# brain.net
KiCad netlist of a schematic drawn in EAGLE
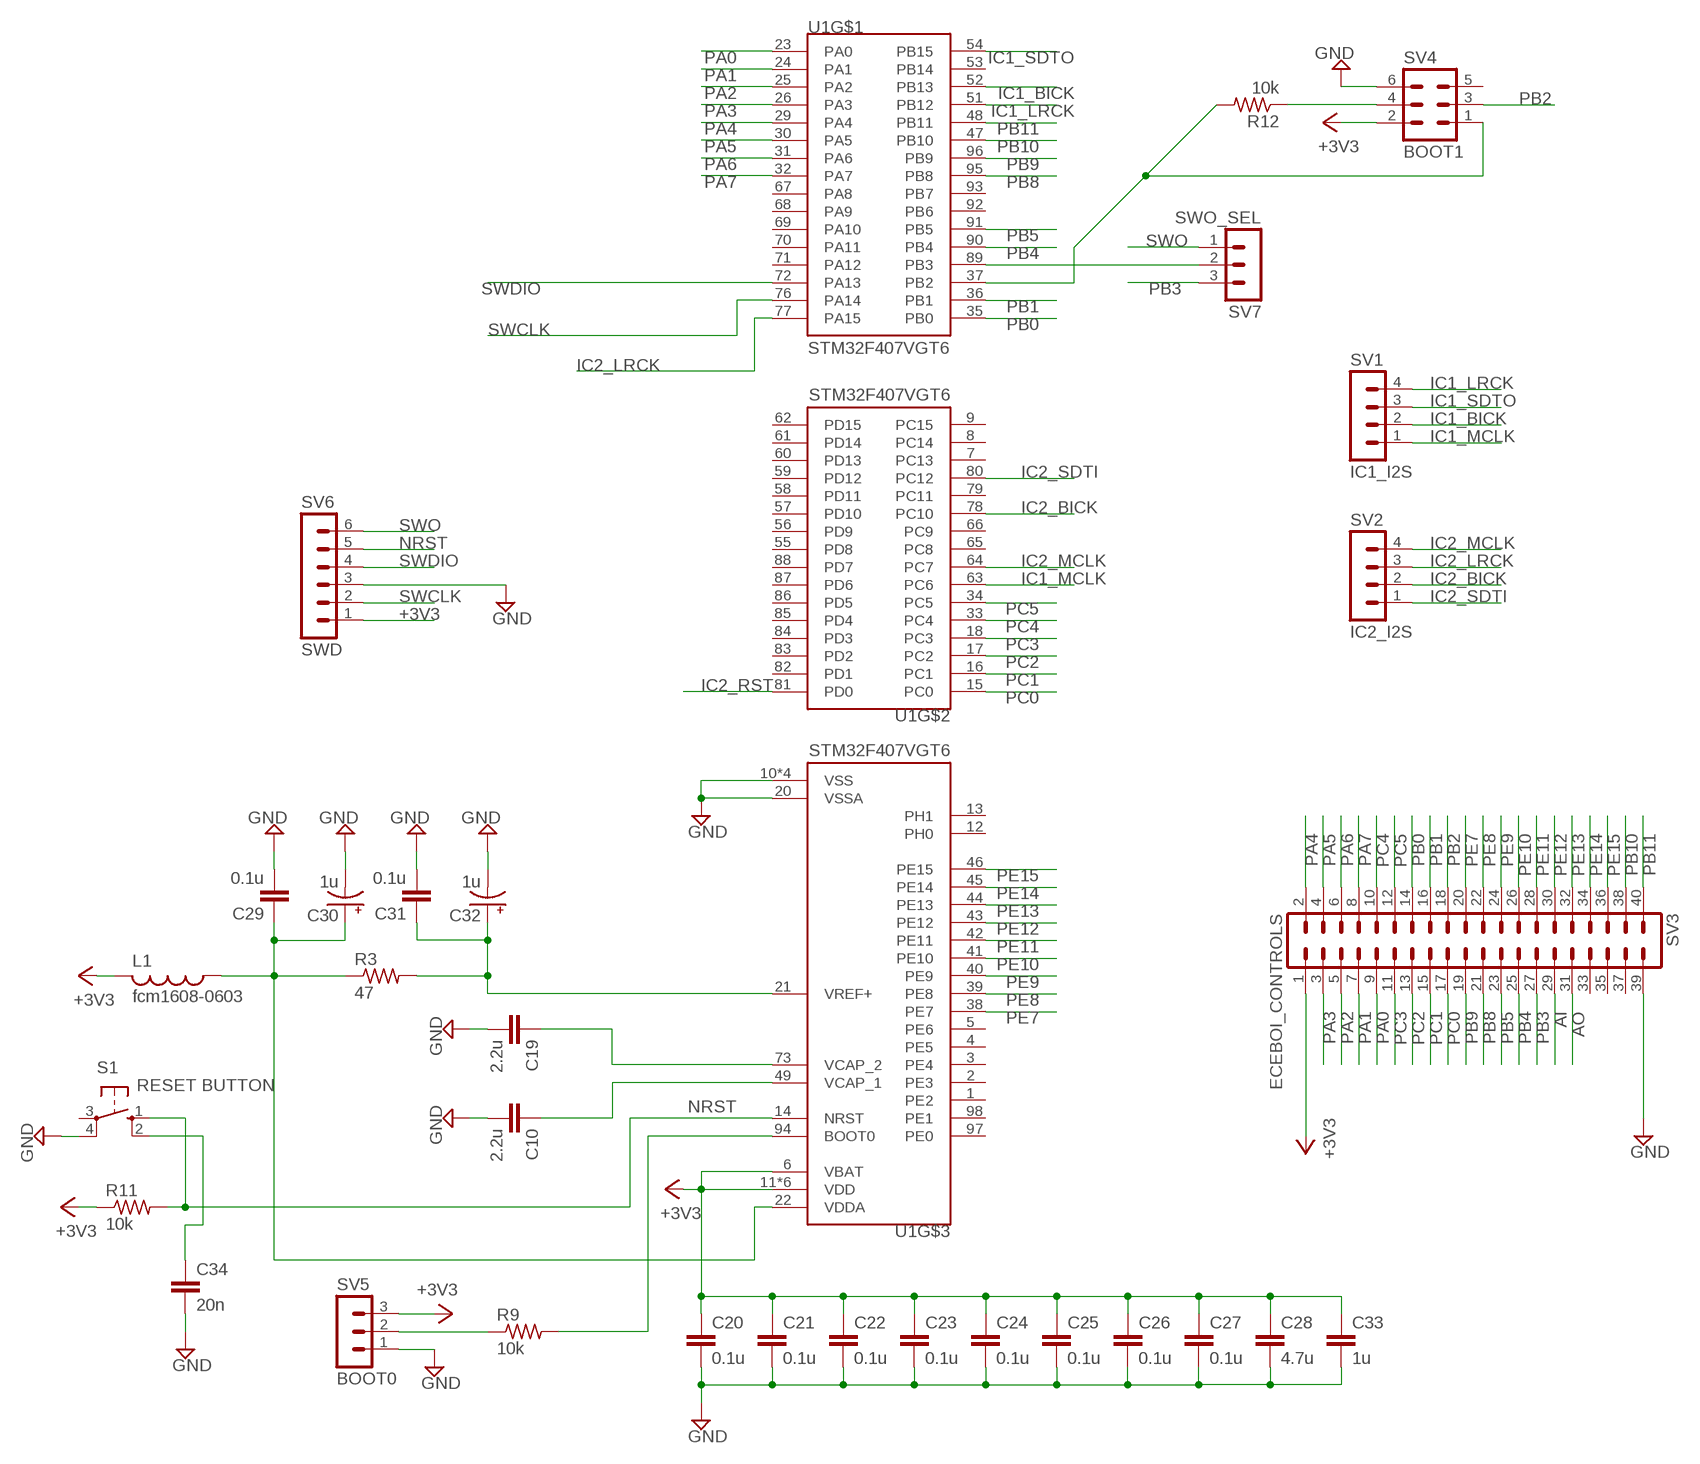
[diagram p0: schematic, sheet 1]
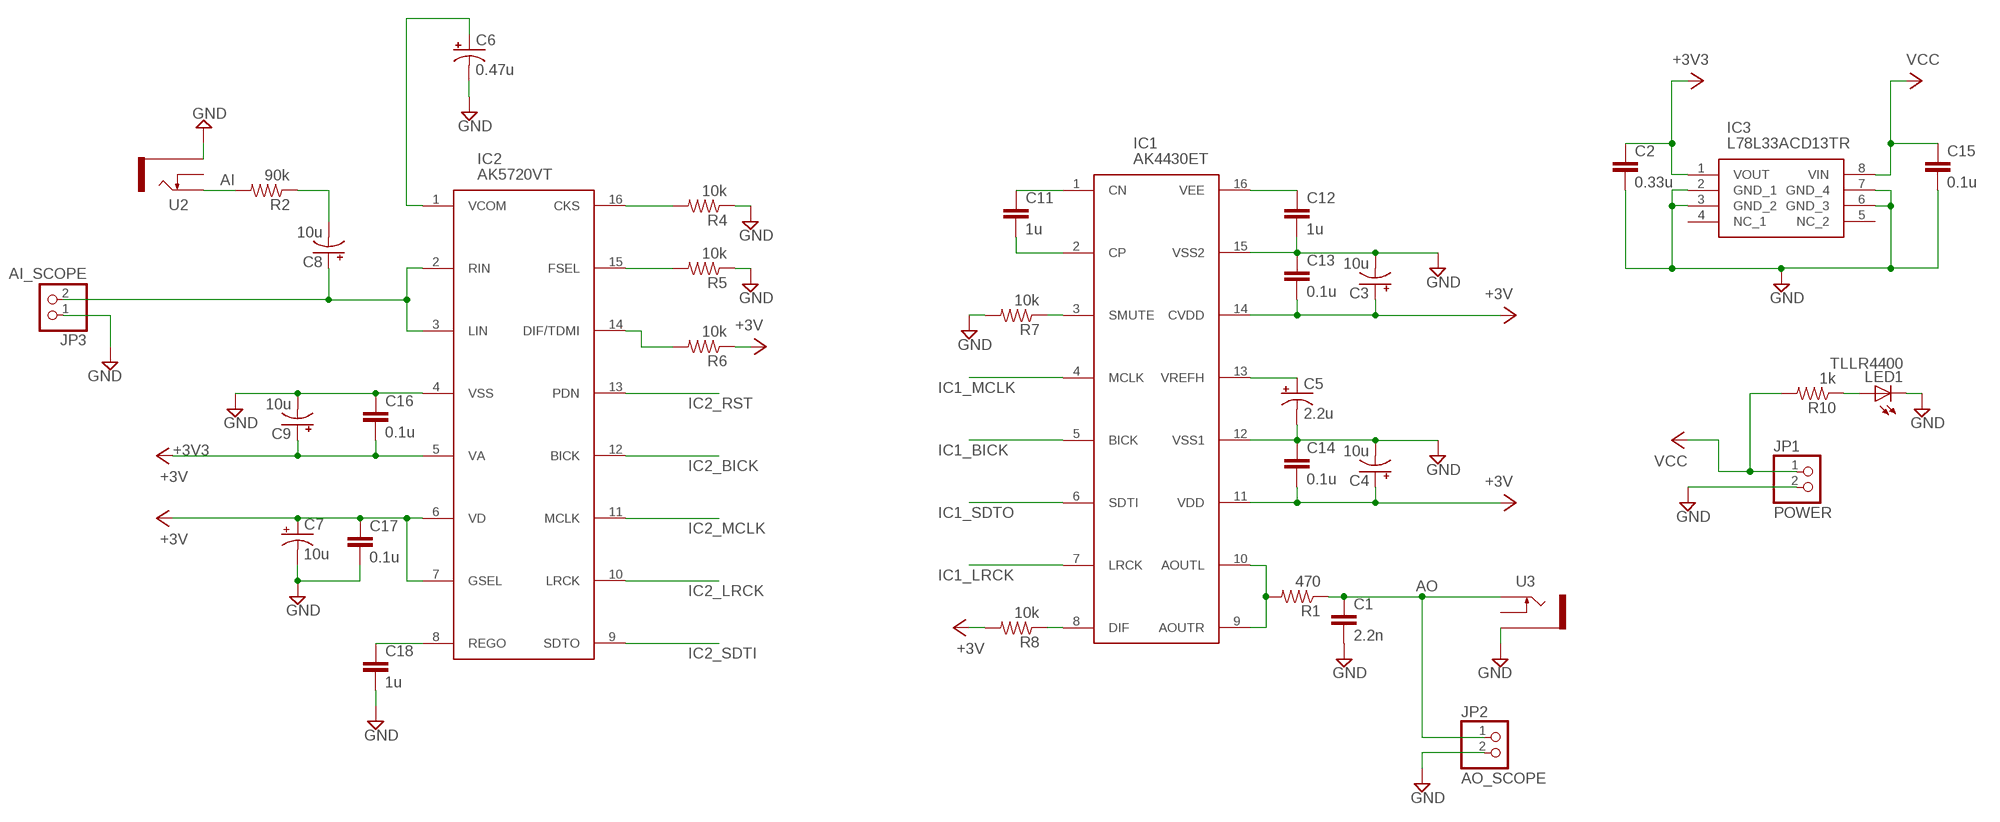
[diagram p1: schematic, sheet 2]

(export (version "E")
  (design (tool "Eeschema 10.0.6"))
  (components
    (comp (ref "C10")
      (value "2.2u")
      (footprint "eagle-import:C025-024X044")
      (libsource (lib "eagle-import") (part "C-EU025-024X044"))
    )
    (comp (ref "C19")
      (value "2.2u")
      (footprint "eagle-import:C025-024X044")
      (libsource (lib "eagle-import") (part "C-EU025-024X044"))
    )
    (comp (ref "C20")
      (value "0.1u")
      (footprint "eagle-import:C025-024X044")
      (libsource (lib "eagle-import") (part "C-EU025-024X044"))
    )
    (comp (ref "C21")
      (value "0.1u")
      (footprint "eagle-import:C025-024X044")
      (libsource (lib "eagle-import") (part "C-EU025-024X044"))
    )
    (comp (ref "C22")
      (value "0.1u")
      (footprint "eagle-import:C025-024X044")
      (libsource (lib "eagle-import") (part "C-EU025-024X044"))
    )
    (comp (ref "C23")
      (value "0.1u")
      (footprint "eagle-import:C025-024X044")
      (libsource (lib "eagle-import") (part "C-EU025-024X044"))
    )
    (comp (ref "C24")
      (value "0.1u")
      (footprint "eagle-import:C025-024X044")
      (libsource (lib "eagle-import") (part "C-EU025-024X044"))
    )
    (comp (ref "C25")
      (value "0.1u")
      (footprint "eagle-import:C025-024X044")
      (libsource (lib "eagle-import") (part "C-EU025-024X044"))
    )
    (comp (ref "C26")
      (value "0.1u")
      (footprint "eagle-import:C025-024X044")
      (libsource (lib "eagle-import") (part "C-EU025-024X044"))
    )
    (comp (ref "C27")
      (value "0.1u")
      (footprint "eagle-import:C025-024X044")
      (libsource (lib "eagle-import") (part "C-EU025-024X044"))
    )
    (comp (ref "C28")
      (value "4.7u")
      (footprint "eagle-import:C025-024X044")
      (libsource (lib "eagle-import") (part "C-EU025-024X044"))
    )
    (comp (ref "C29")
      (value "0.1u")
      (footprint "eagle-import:C025-024X044")
      (libsource (lib "eagle-import") (part "C-EU025-024X044"))
    )
    (comp (ref "C30")
      (value "1u")
      (footprint "eagle-import:E2-5")
      (libsource (lib "eagle-import") (part "CPOL-USE2-5"))
    )
    (comp (ref "C31")
      (value "0.1u")
      (footprint "eagle-import:C025-024X044")
      (libsource (lib "eagle-import") (part "C-EU025-024X044"))
    )
    (comp (ref "C32")
      (value "1u")
      (footprint "eagle-import:E2-5")
      (libsource (lib "eagle-import") (part "CPOL-USE2-5"))
    )
    (comp (ref "C33")
      (value "1u")
      (footprint "eagle-import:C025-024X044")
      (libsource (lib "eagle-import") (part "C-EU025-024X044"))
    )
    (comp (ref "C34")
      (value "20n")
      (footprint "eagle-import:C025-024X044")
      (libsource (lib "eagle-import") (part "C-EU025-024X044"))
    )
    (comp (ref "L1")
      (value "fcm1608-0603")
      (footprint "eagle-import:0207_10")
      (libsource (lib "eagle-import") (part "L-US0207/10"))
    )
    (comp (ref "R3")
      (value "47")
      (footprint "eagle-import:0207_10")
      (libsource (lib "eagle-import") (part "R-US_0207/10"))
    )
    (comp (ref "R9")
      (value "10k")
      (footprint "eagle-import:0207_10")
      (libsource (lib "eagle-import") (part "R-US_0207/10"))
    )
    (comp (ref "R11")
      (value "10k")
      (footprint "eagle-import:0207_10")
      (libsource (lib "eagle-import") (part "R-US_0207/10"))
    )
    (comp (ref "R12")
      (value "10k")
      (footprint "eagle-import:0207_10")
      (libsource (lib "eagle-import") (part "R-US_0207/10"))
    )
    (comp (ref "S1")
      (value "RESET BUTTON")
      (footprint "eagle-import:B3F-10XX")
      (fields (field (name "MPN") "B3F-1000"))
      (libsource (lib "eagle-import") (part "10-XX"))
    )
    (comp (ref "SV1")
      (value "IC1_I2S")
      (footprint "eagle-import:MA04-1")
      (libsource (lib "eagle-import") (part "MA04-1"))
    )
    (comp (ref "SV2")
      (value "IC2_I2S")
      (footprint "eagle-import:MA04-1")
      (libsource (lib "eagle-import") (part "MA04-1"))
    )
    (comp (ref "SV3")
      (value "ECEBOI_CONTROLS")
      (footprint "eagle-import:MA20-2")
      (libsource (lib "eagle-import") (part "MA20-2"))
    )
    (comp (ref "SV4")
      (value "BOOT1")
      (footprint "eagle-import:MA03-2")
      (libsource (lib "eagle-import") (part "MA03-2"))
    )
    (comp (ref "SV5")
      (value "BOOT0")
      (footprint "eagle-import:MA03-1")
      (libsource (lib "eagle-import") (part "MA03-1"))
    )
    (comp (ref "SV6")
      (value "SWD")
      (footprint "eagle-import:MA06-1")
      (libsource (lib "eagle-import") (part "MA06-1"))
    )
    (comp (ref "SV7")
      (value "SWO_SEL")
      (footprint "eagle-import:MA03-1")
      (libsource (lib "eagle-import") (part "MA03-1"))
    )
    (comp (ref "U1")
      (value "STM32F407VGT6")
      (footprint "eagle-import:QFP50P1600X1600X160-100N")
      (fields (field (name "DIGI-KEY_PART_NUMBER") "497-11605-ND") (field (name "MF") "STMicroelectronics"))
      (libsource (lib "eagle-import") (part "STM32F407VGT6"))
    )
    (comp (ref "C1")
      (value "2.2n")
      (footprint "eagle-import:C025-024X044")
      (libsource (lib "eagle-import") (part "C-EU025-024X044"))
    )
    (comp (ref "C2")
      (value "0.33u")
      (footprint "eagle-import:C025-024X044")
      (libsource (lib "eagle-import") (part "C-EU025-024X044"))
    )
    (comp (ref "C3")
      (value "10u")
      (footprint "eagle-import:E2-5")
      (libsource (lib "eagle-import") (part "CPOL-USE2-5"))
    )
    (comp (ref "C4")
      (value "10u")
      (footprint "eagle-import:E2-5")
      (libsource (lib "eagle-import") (part "CPOL-USE2-5"))
    )
    (comp (ref "C5")
      (value "2.2u")
      (footprint "eagle-import:E2-5")
      (libsource (lib "eagle-import") (part "CPOL-USE2-5"))
    )
    (comp (ref "C6")
      (value "0.47u")
      (footprint "eagle-import:E2-5")
      (libsource (lib "eagle-import") (part "CPOL-USE2-5"))
    )
    (comp (ref "C7")
      (value "10u")
      (footprint "eagle-import:E2-5")
      (libsource (lib "eagle-import") (part "CPOL-USE2-5"))
    )
    (comp (ref "C8")
      (value "10u")
      (footprint "eagle-import:E2-5")
      (libsource (lib "eagle-import") (part "CPOL-USE2-5"))
    )
    (comp (ref "C9")
      (value "10u")
      (footprint "eagle-import:E2-5")
      (libsource (lib "eagle-import") (part "CPOL-USE2-5"))
    )
    (comp (ref "C11")
      (value "1u")
      (footprint "eagle-import:C025-024X044")
      (libsource (lib "eagle-import") (part "C-EU025-024X044"))
    )
    (comp (ref "C12")
      (value "1u")
      (footprint "eagle-import:C025-024X044")
      (libsource (lib "eagle-import") (part "C-EU025-024X044"))
    )
    (comp (ref "C13")
      (value "0.1u")
      (footprint "eagle-import:C025-024X044")
      (libsource (lib "eagle-import") (part "C-EU025-024X044"))
    )
    (comp (ref "C14")
      (value "0.1u")
      (footprint "eagle-import:C025-024X044")
      (libsource (lib "eagle-import") (part "C-EU025-024X044"))
    )
    (comp (ref "C15")
      (value "0.1u")
      (footprint "eagle-import:C025-024X044")
      (libsource (lib "eagle-import") (part "C-EU025-024X044"))
    )
    (comp (ref "C16")
      (value "0.1u")
      (footprint "eagle-import:C025-024X044")
      (libsource (lib "eagle-import") (part "C-EU025-024X044"))
    )
    (comp (ref "C17")
      (value "0.1u")
      (footprint "eagle-import:C025-024X044")
      (libsource (lib "eagle-import") (part "C-EU025-024X044"))
    )
    (comp (ref "C18")
      (value "1u")
      (footprint "eagle-import:C025-024X044")
      (libsource (lib "eagle-import") (part "C-EU025-024X044"))
    )
    (comp (ref "IC1")
      (value "AK4430ET")
      (footprint "eagle-import:SOP65P640X110-16N")
      (libsource (lib "eagle-import") (part "AK4430ET"))
    )
    (comp (ref "IC2")
      (value "AK5720VT")
      (footprint "eagle-import:SOP65P640X110-16N")
      (libsource (lib "eagle-import") (part "AK5720VT"))
    )
    (comp (ref "IC3")
      (value "L78L33ACD13TR")
      (footprint "eagle-import:SOIC127P600X175-8N")
      (libsource (lib "eagle-import") (part "L78L33ACD13TR"))
    )
    (comp (ref "JP1")
      (value "POWER")
      (footprint "eagle-import:1X02")
      (libsource (lib "eagle-import") (part "PINHD-1X2"))
    )
    (comp (ref "JP2")
      (value "AO_SCOPE")
      (footprint "eagle-import:1X02")
      (libsource (lib "eagle-import") (part "pinhead_325_PINHD-1X2"))
    )
    (comp (ref "JP3")
      (value "AI_SCOPE")
      (footprint "eagle-import:1X02")
      (libsource (lib "eagle-import") (part "pinhead_325_PINHD-1X2"))
    )
    (comp (ref "LED1")
      (value "TLLR4400")
      (footprint "eagle-import:LED3MM")
      (fields (field (name "MF") "VISHAY SEMICONDUCTOR"))
      (libsource (lib "eagle-import") (part "TLLR4400"))
    )
    (comp (ref "R1")
      (value "470")
      (footprint "eagle-import:0207_10")
      (libsource (lib "eagle-import") (part "R-US_0207/10"))
    )
    (comp (ref "R2")
      (value "90k")
      (footprint "eagle-import:0207_10")
      (libsource (lib "eagle-import") (part "R-US_0207/10"))
    )
    (comp (ref "R4")
      (value "10k")
      (footprint "eagle-import:0207_10")
      (libsource (lib "eagle-import") (part "R-US_0207/10"))
    )
    (comp (ref "R5")
      (value "10k")
      (footprint "eagle-import:0207_10")
      (libsource (lib "eagle-import") (part "R-US_0207/10"))
    )
    (comp (ref "R6")
      (value "10k")
      (footprint "eagle-import:0207_10")
      (libsource (lib "eagle-import") (part "R-US_0207/10"))
    )
    (comp (ref "R7")
      (value "10k")
      (footprint "eagle-import:0207_10")
      (libsource (lib "eagle-import") (part "R-US_0207/10"))
    )
    (comp (ref "R8")
      (value "10k")
      (footprint "eagle-import:0207_10")
      (libsource (lib "eagle-import") (part "R-US_0207/10"))
    )
    (comp (ref "R10")
      (value "1k")
      (footprint "eagle-import:0207_10")
      (libsource (lib "eagle-import") (part "R-US_0207/10"))
    )
    (comp (ref "U2")
      (value "THONKICONNNEW")
      (footprint "eagle-import:WQP-PJ301M-12_JACK")
      (libsource (lib "eagle-import") (part "THONKICONNNEW"))
    )
    (comp (ref "U3")
      (value "THONKICONNNEW")
      (footprint "eagle-import:WQP-PJ301M-12_JACK")
      (libsource (lib "eagle-import") (part "THONKICONNNEW"))
    )
  )
  (nets
    (net (code "1") (name "+3V3") (class "Default")
      (node (ref "C13") (pin "2") (pinfunction "2_2") (pintype "passive"))
      (node (ref "C14") (pin "2") (pinfunction "2_2") (pintype "passive"))
      (node (ref "C16") (pin "2") (pinfunction "2_2") (pintype "passive"))
      (node (ref "C17") (pin "1") (pinfunction "1_1") (pintype "passive"))
      (node (ref "C2") (pin "1") (pinfunction "1_1") (pintype "passive"))
      (node (ref "C20") (pin "1") (pinfunction "1_1") (pintype "passive"))
      (node (ref "C21") (pin "1") (pinfunction "1_1") (pintype "passive"))
      (node (ref "C22") (pin "1") (pinfunction "1_1") (pintype "passive"))
      (node (ref "C23") (pin "1") (pinfunction "1_1") (pintype "passive"))
      (node (ref "C24") (pin "1") (pinfunction "1_1") (pintype "passive"))
      (node (ref "C25") (pin "1") (pinfunction "1_1") (pintype "passive"))
      (node (ref "C26") (pin "1") (pinfunction "1_1") (pintype "passive"))
      (node (ref "C27") (pin "1") (pinfunction "1_1") (pintype "passive"))
      (node (ref "C28") (pin "1") (pinfunction "1_1") (pintype "passive"))
      (node (ref "C3") (pin "+") (pinfunction "+_+") (pintype "passive"))
      (node (ref "C33") (pin "1") (pinfunction "1_1") (pintype "passive"))
      (node (ref "C4") (pin "+") (pinfunction "+_+") (pintype "passive"))
      (node (ref "C7") (pin "+") (pinfunction "+_+") (pintype "passive"))
      (node (ref "C9") (pin "+") (pinfunction "+_+") (pintype "passive"))
      (node (ref "IC1") (pin "11") (pinfunction "VDD_11") (pintype "power_in"))
      (node (ref "IC1") (pin "14") (pinfunction "CVDD_14") (pintype "power_in"))
      (node (ref "IC2") (pin "5") (pinfunction "VA_5") (pintype "power_in"))
      (node (ref "IC2") (pin "6") (pinfunction "VD_6") (pintype "power_in"))
      (node (ref "IC2") (pin "7") (pinfunction "GSEL_7") (pintype "input"))
      (node (ref "IC3") (pin "1") (pinfunction "VOUT_1") (pintype "output"))
      (node (ref "L1") (pin "2") (pinfunction "2_2") (pintype "passive"))
      (node (ref "R11") (pin "1") (pinfunction "1_1") (pintype "passive"))
      (node (ref "R6") (pin "1") (pinfunction "1_1") (pintype "passive"))
      (node (ref "R8") (pin "2") (pinfunction "2_2") (pintype "passive"))
      (node (ref "SV3") (pin "1") (pinfunction "1_1") (pintype "passive"))
      (node (ref "SV4") (pin "2") (pinfunction "2_2") (pintype "passive"))
      (node (ref "SV5") (pin "3") (pinfunction "3_3") (pintype "passive"))
      (node (ref "SV6") (pin "1") (pinfunction "1_1") (pintype "passive"))
      (node (ref "U1") (pin "100") (pinfunction "VDD_100") (pintype "power_in"))
      (node (ref "U1") (pin "11") (pinfunction "VDD_11") (pintype "power_in"))
      (node (ref "U1") (pin "19") (pinfunction "VDD_19") (pintype "power_in"))
      (node (ref "U1") (pin "28") (pinfunction "VDD_28") (pintype "power_in"))
      (node (ref "U1") (pin "50") (pinfunction "VDD_50") (pintype "power_in"))
      (node (ref "U1") (pin "6") (pinfunction "VBAT_6") (pintype "power_in"))
      (node (ref "U1") (pin "75") (pinfunction "VDD_75") (pintype "power_in"))
    )
    (net (code "2") (name "AI") (class "Default")
      (node (ref "R2") (pin "2") (pinfunction "2_2") (pintype "passive"))
      (node (ref "SV3") (pin "29") (pinfunction "29_29") (pintype "passive"))
      (node (ref "U2") (pin "P$1_TIP") (pinfunction "TIP_P$1_TIP") (pintype "passive"))
    )
    (net (code "3") (name "AO") (class "Default")
      (node (ref "C1") (pin "1") (pinfunction "1_1") (pintype "passive"))
      (node (ref "JP2") (pin "1") (pinfunction "1_1") (pintype "passive"))
      (node (ref "R1") (pin "1") (pinfunction "1_1") (pintype "passive"))
      (node (ref "SV3") (pin "31") (pinfunction "31_31") (pintype "passive"))
      (node (ref "U3") (pin "P$1_TIP") (pinfunction "TIP_P$1_TIP") (pintype "passive"))
    )
    (net (code "4") (name "GND") (class "Default")
      (node (ref "C1") (pin "2") (pinfunction "2_2") (pintype "passive"))
      (node (ref "C10") (pin "2") (pinfunction "2_2") (pintype "passive"))
      (node (ref "C12") (pin "2") (pinfunction "2_2") (pintype "passive"))
      (node (ref "C13") (pin "1") (pinfunction "1_1") (pintype "passive"))
      (node (ref "C14") (pin "1") (pinfunction "1_1") (pintype "passive"))
      (node (ref "C15") (pin "2") (pinfunction "2_2") (pintype "passive"))
      (node (ref "C16") (pin "1") (pinfunction "1_1") (pintype "passive"))
      (node (ref "C17") (pin "2") (pinfunction "2_2") (pintype "passive"))
      (node (ref "C18") (pin "2") (pinfunction "2_2") (pintype "passive"))
      (node (ref "C19") (pin "2") (pinfunction "2_2") (pintype "passive"))
      (node (ref "C2") (pin "2") (pinfunction "2_2") (pintype "passive"))
      (node (ref "C20") (pin "2") (pinfunction "2_2") (pintype "passive"))
      (node (ref "C21") (pin "2") (pinfunction "2_2") (pintype "passive"))
      (node (ref "C22") (pin "2") (pinfunction "2_2") (pintype "passive"))
      (node (ref "C23") (pin "2") (pinfunction "2_2") (pintype "passive"))
      (node (ref "C24") (pin "2") (pinfunction "2_2") (pintype "passive"))
      (node (ref "C25") (pin "2") (pinfunction "2_2") (pintype "passive"))
      (node (ref "C26") (pin "2") (pinfunction "2_2") (pintype "passive"))
      (node (ref "C27") (pin "2") (pinfunction "2_2") (pintype "passive"))
      (node (ref "C28") (pin "2") (pinfunction "2_2") (pintype "passive"))
      (node (ref "C29") (pin "2") (pinfunction "2_2") (pintype "passive"))
      (node (ref "C3") (pin "-") (pinfunction "-_-") (pintype "passive"))
      (node (ref "C30") (pin "-") (pinfunction "-_-") (pintype "passive"))
      (node (ref "C31") (pin "2") (pinfunction "2_2") (pintype "passive"))
      (node (ref "C32") (pin "-") (pinfunction "-_-") (pintype "passive"))
      (node (ref "C33") (pin "2") (pinfunction "2_2") (pintype "passive"))
      (node (ref "C34") (pin "2") (pinfunction "2_2") (pintype "passive"))
      (node (ref "C4") (pin "-") (pinfunction "-_-") (pintype "passive"))
      (node (ref "C5") (pin "-") (pinfunction "-_-") (pintype "passive"))
      (node (ref "C6") (pin "-") (pinfunction "-_-") (pintype "passive"))
      (node (ref "C7") (pin "-") (pinfunction "-_-") (pintype "passive"))
      (node (ref "C9") (pin "-") (pinfunction "-_-") (pintype "passive"))
      (node (ref "IC1") (pin "12") (pinfunction "VSS1_12") (pintype "power_in"))
      (node (ref "IC1") (pin "15") (pinfunction "VSS2_15") (pintype "power_in"))
      (node (ref "IC2") (pin "4") (pinfunction "VSS_4") (pintype "power_in"))
      (node (ref "IC3") (pin "2") (pinfunction "GND_1_2") (pintype "power_in"))
      (node (ref "IC3") (pin "3") (pinfunction "GND_2_3") (pintype "power_in"))
      (node (ref "IC3") (pin "6") (pinfunction "GND_3_6") (pintype "power_in"))
      (node (ref "IC3") (pin "7") (pinfunction "GND_4_7") (pintype "power_in"))
      (node (ref "JP1") (pin "2") (pinfunction "2_2") (pintype "passive"))
      (node (ref "JP2") (pin "2") (pinfunction "2_2") (pintype "passive"))
      (node (ref "JP3") (pin "1") (pinfunction "1_1") (pintype "passive"))
      (node (ref "LED1") (pin "K") (pinfunction "C_K") (pintype "passive"))
      (node (ref "R4") (pin "1") (pinfunction "1_1") (pintype "passive"))
      (node (ref "R5") (pin "1") (pinfunction "1_1") (pintype "passive"))
      (node (ref "R7") (pin "2") (pinfunction "2_2") (pintype "passive"))
      (node (ref "S1") (pin "4") (pinfunction "P1_4") (pintype "passive"))
      (node (ref "SV3") (pin "39") (pinfunction "39_39") (pintype "passive"))
      (node (ref "SV4") (pin "6") (pinfunction "6_6") (pintype "passive"))
      (node (ref "SV5") (pin "1") (pinfunction "1_1") (pintype "passive"))
      (node (ref "SV6") (pin "3") (pinfunction "3_3") (pintype "passive"))
      (node (ref "U1") (pin "10") (pinfunction "VSS_10") (pintype "power_in"))
      (node (ref "U1") (pin "20") (pinfunction "VSSA_20") (pintype "power_in"))
      (node (ref "U1") (pin "27") (pinfunction "VSS_27") (pintype "power_in"))
      (node (ref "U1") (pin "74") (pinfunction "VSS_74") (pintype "power_in"))
      (node (ref "U1") (pin "99") (pinfunction "VSS_99") (pintype "power_in"))
      (node (ref "U2") (pin "P$3_SLEEVE") (pinfunction "SLEEVE_P$3_SLEEVE") (pintype "passive"))
      (node (ref "U3") (pin "P$3_SLEEVE") (pinfunction "SLEEVE_P$3_SLEEVE") (pintype "passive"))
    )
    (net (code "5") (name "IC1_BICK") (class "Default")
      (node (ref "IC1") (pin "5") (pinfunction "BICK_5") (pintype "input"))
      (node (ref "SV1") (pin "2") (pinfunction "2_2") (pintype "passive"))
      (node (ref "U1") (pin "52") (pinfunction "PB13_52") (pintype "bidirectional"))
    )
    (net (code "6") (name "IC1_LRCK") (class "Default")
      (node (ref "IC1") (pin "7") (pinfunction "LRCK_7") (pintype "input"))
      (node (ref "SV1") (pin "4") (pinfunction "4_4") (pintype "passive"))
      (node (ref "U1") (pin "51") (pinfunction "PB12_51") (pintype "bidirectional"))
    )
    (net (code "7") (name "IC1_MCLK") (class "Default")
      (node (ref "IC1") (pin "4") (pinfunction "MCLK_4") (pintype "input"))
      (node (ref "SV1") (pin "1") (pinfunction "1_1") (pintype "passive"))
      (node (ref "U1") (pin "63") (pinfunction "PC6_63") (pintype "bidirectional"))
    )
    (net (code "8") (name "IC1_SDTO") (class "Default")
      (node (ref "IC1") (pin "6") (pinfunction "SDTI_6") (pintype "input"))
      (node (ref "SV1") (pin "3") (pinfunction "3_3") (pintype "passive"))
      (node (ref "U1") (pin "54") (pinfunction "PB15_54") (pintype "bidirectional"))
    )
    (net (code "9") (name "IC2_BICK") (class "Default")
      (node (ref "IC2") (pin "12") (pinfunction "BICK_12") (pintype "input"))
      (node (ref "SV2") (pin "2") (pinfunction "2_2") (pintype "passive"))
      (node (ref "U1") (pin "78") (pinfunction "PC10_78") (pintype "bidirectional"))
    )
    (net (code "10") (name "IC2_LRCK") (class "Default")
      (node (ref "IC2") (pin "10") (pinfunction "LRCK_10") (pintype "input"))
      (node (ref "SV2") (pin "3") (pinfunction "3_3") (pintype "passive"))
      (node (ref "U1") (pin "77") (pinfunction "PA15_77") (pintype "bidirectional"))
    )
    (net (code "11") (name "IC2_MCLK") (class "Default")
      (node (ref "IC2") (pin "11") (pinfunction "MCLK_11") (pintype "input"))
      (node (ref "SV2") (pin "4") (pinfunction "4_4") (pintype "passive"))
      (node (ref "U1") (pin "64") (pinfunction "PC7_64") (pintype "bidirectional"))
    )
    (net (code "12") (name "IC2_RST") (class "Default")
      (node (ref "IC2") (pin "13") (pinfunction "PDN_13") (pintype "input"))
      (node (ref "U1") (pin "81") (pinfunction "PD0_81") (pintype "bidirectional"))
    )
    (net (code "13") (name "IC2_SDTI") (class "Default")
      (node (ref "IC2") (pin "9") (pinfunction "SDTO_9") (pintype "output"))
      (node (ref "SV2") (pin "1") (pinfunction "1_1") (pintype "passive"))
      (node (ref "U1") (pin "80") (pinfunction "PC12_80") (pintype "bidirectional"))
    )
    (net (code "14") (name "NRST") (class "Default")
      (node (ref "R11") (pin "2") (pinfunction "2_2") (pintype "passive"))
      (node (ref "S1") (pin "1") (pinfunction "S_1") (pintype "passive"))
      (node (ref "SV6") (pin "5") (pinfunction "5_5") (pintype "passive"))
      (node (ref "U1") (pin "14") (pinfunction "NRST_14") (pintype "bidirectional"))
    )
    (net (code "15") (name "Net-(C8-Pad-)") (class "Default")
      (node (ref "C8") (pin "-") (pinfunction "-_-") (pintype "passive"))
      (node (ref "R2") (pin "1") (pinfunction "1_1") (pintype "passive"))
    )
    (net (code "16") (name "Net-(IC1-AOUTL)") (class "Default")
      (node (ref "IC1") (pin "10") (pinfunction "AOUTL_10") (pintype "output"))
      (node (ref "IC1") (pin "9") (pinfunction "AOUTR_9") (pintype "output"))
      (node (ref "R1") (pin "2") (pinfunction "2_2") (pintype "passive"))
    )
    (net (code "17") (name "Net-(IC1-CN)") (class "Default")
      (node (ref "C11") (pin "1") (pinfunction "1_1") (pintype "passive"))
      (node (ref "IC1") (pin "1") (pinfunction "CN_1") (pintype "input"))
    )
    (net (code "18") (name "Net-(IC1-CP)") (class "Default")
      (node (ref "C11") (pin "2") (pinfunction "2_2") (pintype "passive"))
      (node (ref "IC1") (pin "2") (pinfunction "CP_2") (pintype "input"))
    )
    (net (code "19") (name "Net-(IC1-DIF)") (class "Default")
      (node (ref "IC1") (pin "8") (pinfunction "DIF_8") (pintype "input"))
      (node (ref "R8") (pin "1") (pinfunction "1_1") (pintype "passive"))
    )
    (net (code "20") (name "Net-(IC1-SMUTE)") (class "Default")
      (node (ref "IC1") (pin "3") (pinfunction "SMUTE_3") (pintype "input"))
      (node (ref "R7") (pin "1") (pinfunction "1_1") (pintype "passive"))
    )
    (net (code "21") (name "Net-(IC1-VEE)") (class "Default")
      (node (ref "C12") (pin "1") (pinfunction "1_1") (pintype "passive"))
      (node (ref "IC1") (pin "16") (pinfunction "VEE_16") (pintype "output"))
    )
    (net (code "22") (name "Net-(IC1-VREFH)") (class "Default")
      (node (ref "C5") (pin "+") (pinfunction "+_+") (pintype "passive"))
      (node (ref "IC1") (pin "13") (pinfunction "VREFH_13") (pintype "output"))
    )
    (net (code "23") (name "Net-(IC2-CKS)") (class "Default")
      (node (ref "IC2") (pin "16") (pinfunction "CKS_16") (pintype "input"))
      (node (ref "R4") (pin "2") (pinfunction "2_2") (pintype "passive"))
    )
    (net (code "24") (name "Net-(IC2-DIF{slash}TDMI)") (class "Default")
      (node (ref "IC2") (pin "14") (pinfunction "DIF/TDMI_14") (pintype "input"))
      (node (ref "R6") (pin "2") (pinfunction "2_2") (pintype "passive"))
    )
    (net (code "25") (name "Net-(IC2-FSEL)") (class "Default")
      (node (ref "IC2") (pin "15") (pinfunction "FSEL_15") (pintype "input"))
      (node (ref "R5") (pin "2") (pinfunction "2_2") (pintype "passive"))
    )
    (net (code "26") (name "Net-(IC2-LIN)") (class "Default")
      (node (ref "C8") (pin "+") (pinfunction "+_+") (pintype "passive"))
      (node (ref "IC2") (pin "2") (pinfunction "RIN_2") (pintype "input"))
      (node (ref "IC2") (pin "3") (pinfunction "LIN_3") (pintype "input"))
      (node (ref "JP3") (pin "2") (pinfunction "2_2") (pintype "passive"))
    )
    (net (code "27") (name "Net-(IC2-REGO)") (class "Default")
      (node (ref "C18") (pin "1") (pinfunction "1_1") (pintype "passive"))
      (node (ref "IC2") (pin "8") (pinfunction "REGO_8") (pintype "output"))
    )
    (net (code "28") (name "Net-(IC2-VCOM)") (class "Default")
      (node (ref "C6") (pin "+") (pinfunction "+_+") (pintype "passive"))
      (node (ref "IC2") (pin "1") (pinfunction "VCOM_1") (pintype "power_in"))
    )
    (net (code "29") (name "Net-(LED1-PadA)") (class "Default")
      (node (ref "LED1") (pin "A") (pinfunction "A_A") (pintype "passive"))
      (node (ref "R10") (pin "1") (pinfunction "1_1") (pintype "passive"))
    )
    (net (code "30") (name "Net-(R9-Pad1)") (class "Default")
      (node (ref "R9") (pin "1") (pinfunction "1_1") (pintype "passive"))
      (node (ref "SV5") (pin "2") (pinfunction "2_2") (pintype "passive"))
    )
    (net (code "31") (name "Net-(R12-Pad1)") (class "Default")
      (node (ref "R12") (pin "1") (pinfunction "1_1") (pintype "passive"))
      (node (ref "SV4") (pin "4") (pinfunction "4_4") (pintype "passive"))
    )
    (net (code "32") (name "Net-(S1-S1)") (class "Default")
      (node (ref "C34") (pin "1") (pinfunction "1_1") (pintype "passive"))
      (node (ref "S1") (pin "2") (pinfunction "S1_2") (pintype "passive"))
    )
    (net (code "33") (name "Net-(U1A-PB2)") (class "Default")
      (node (ref "R12") (pin "2") (pinfunction "2_2") (pintype "passive"))
      (node (ref "SV4") (pin "1") (pinfunction "1_1") (pintype "passive"))
      (node (ref "U1") (pin "37") (pinfunction "PB2_37") (pintype "bidirectional"))
    )
    (net (code "34") (name "Net-(U1A-PB3)") (class "Default")
      (node (ref "SV7") (pin "2") (pinfunction "2_2") (pintype "passive"))
      (node (ref "U1") (pin "89") (pinfunction "PB3_89") (pintype "bidirectional"))
    )
    (net (code "35") (name "Net-(U1C-BOOT0)") (class "Default")
      (node (ref "R9") (pin "2") (pinfunction "2_2") (pintype "passive"))
      (node (ref "U1") (pin "94") (pinfunction "BOOT0_94") (pintype "input"))
    )
    (net (code "36") (name "Net-(U1C-VCAP_1)") (class "Default")
      (node (ref "C10") (pin "1") (pinfunction "1_1") (pintype "passive"))
      (node (ref "U1") (pin "49") (pinfunction "VCAP_1_49") (pintype "passive"))
    )
    (net (code "37") (name "Net-(U1C-VCAP_2)") (class "Default")
      (node (ref "C19") (pin "1") (pinfunction "1_1") (pintype "passive"))
      (node (ref "U1") (pin "73") (pinfunction "VCAP_2_73") (pintype "passive"))
    )
    (net (code "38") (name "Net-(U1C-VDDA)") (class "Default")
      (node (ref "C29") (pin "1") (pinfunction "1_1") (pintype "passive"))
      (node (ref "C30") (pin "+") (pinfunction "+_+") (pintype "passive"))
      (node (ref "L1") (pin "1") (pinfunction "1_1") (pintype "passive"))
      (node (ref "R3") (pin "1") (pinfunction "1_1") (pintype "passive"))
      (node (ref "U1") (pin "22") (pinfunction "VDDA_22") (pintype "power_in"))
    )
    (net (code "39") (name "Net-(U1C-VREF+)") (class "Default")
      (node (ref "C31") (pin "1") (pinfunction "1_1") (pintype "passive"))
      (node (ref "C32") (pin "+") (pinfunction "+_+") (pintype "passive"))
      (node (ref "R3") (pin "2") (pinfunction "2_2") (pintype "passive"))
      (node (ref "U1") (pin "21") (pinfunction "VREF+_21") (pintype "power_in"))
    )
    (net (code "40") (name "PA0") (class "Default")
      (node (ref "SV3") (pin "9") (pinfunction "9_9") (pintype "passive"))
      (node (ref "U1") (pin "23") (pinfunction "PA0_23") (pintype "bidirectional"))
    )
    (net (code "41") (name "PA1") (class "Default")
      (node (ref "SV3") (pin "7") (pinfunction "7_7") (pintype "passive"))
      (node (ref "U1") (pin "24") (pinfunction "PA1_24") (pintype "bidirectional"))
    )
    (net (code "42") (name "PA2") (class "Default")
      (node (ref "SV3") (pin "5") (pinfunction "5_5") (pintype "passive"))
      (node (ref "U1") (pin "25") (pinfunction "PA2_25") (pintype "bidirectional"))
    )
    (net (code "43") (name "PA3") (class "Default")
      (node (ref "SV3") (pin "3") (pinfunction "3_3") (pintype "passive"))
      (node (ref "U1") (pin "26") (pinfunction "PA3_26") (pintype "bidirectional"))
    )
    (net (code "44") (name "PA4") (class "Default")
      (node (ref "SV3") (pin "2") (pinfunction "2_2") (pintype "passive"))
      (node (ref "U1") (pin "29") (pinfunction "PA4_29") (pintype "bidirectional"))
    )
    (net (code "45") (name "PA5") (class "Default")
      (node (ref "SV3") (pin "4") (pinfunction "4_4") (pintype "passive"))
      (node (ref "U1") (pin "30") (pinfunction "PA5_30") (pintype "bidirectional"))
    )
    (net (code "46") (name "PA6") (class "Default")
      (node (ref "SV3") (pin "6") (pinfunction "6_6") (pintype "passive"))
      (node (ref "U1") (pin "31") (pinfunction "PA6_31") (pintype "bidirectional"))
    )
    (net (code "47") (name "PA7") (class "Default")
      (node (ref "SV3") (pin "8") (pinfunction "8_8") (pintype "passive"))
      (node (ref "U1") (pin "32") (pinfunction "PA7_32") (pintype "bidirectional"))
    )
    (net (code "48") (name "PB0") (class "Default")
      (node (ref "SV3") (pin "14") (pinfunction "14_14") (pintype "passive"))
      (node (ref "U1") (pin "35") (pinfunction "PB0_35") (pintype "bidirectional"))
    )
    (net (code "49") (name "PB1") (class "Default")
      (node (ref "SV3") (pin "16") (pinfunction "16_16") (pintype "passive"))
      (node (ref "U1") (pin "36") (pinfunction "PB1_36") (pintype "bidirectional"))
    )
    (net (code "50") (name "PB2") (class "Default")
      (node (ref "SV3") (pin "18") (pinfunction "18_18") (pintype "passive"))
      (node (ref "SV4") (pin "3") (pinfunction "3_3") (pintype "passive"))
    )
    (net (code "51") (name "PB3") (class "Default")
      (node (ref "SV3") (pin "27") (pinfunction "27_27") (pintype "passive"))
      (node (ref "SV7") (pin "3") (pinfunction "3_3") (pintype "passive"))
    )
    (net (code "52") (name "PB4") (class "Default")
      (node (ref "SV3") (pin "25") (pinfunction "25_25") (pintype "passive"))
      (node (ref "U1") (pin "90") (pinfunction "PB4_90") (pintype "bidirectional"))
    )
    (net (code "53") (name "PB5") (class "Default")
      (node (ref "SV3") (pin "23") (pinfunction "23_23") (pintype "passive"))
      (node (ref "U1") (pin "91") (pinfunction "PB5_91") (pintype "bidirectional"))
    )
    (net (code "54") (name "PB8") (class "Default")
      (node (ref "SV3") (pin "21") (pinfunction "21_21") (pintype "passive"))
      (node (ref "U1") (pin "95") (pinfunction "PB8_95") (pintype "bidirectional"))
    )
    (net (code "55") (name "PB9") (class "Default")
      (node (ref "SV3") (pin "19") (pinfunction "19_19") (pintype "passive"))
      (node (ref "U1") (pin "96") (pinfunction "PB9_96") (pintype "bidirectional"))
    )
    (net (code "56") (name "PB10") (class "Default")
      (node (ref "SV3") (pin "38") (pinfunction "38_38") (pintype "passive"))
      (node (ref "U1") (pin "47") (pinfunction "PB10_47") (pintype "bidirectional"))
    )
    (net (code "57") (name "PB11") (class "Default")
      (node (ref "SV3") (pin "40") (pinfunction "40_40") (pintype "passive"))
      (node (ref "U1") (pin "48") (pinfunction "PB11_48") (pintype "bidirectional"))
    )
    (net (code "58") (name "PC0") (class "Default")
      (node (ref "SV3") (pin "17") (pinfunction "17_17") (pintype "passive"))
      (node (ref "U1") (pin "15") (pinfunction "PC0_15") (pintype "bidirectional"))
    )
    (net (code "59") (name "PC1") (class "Default")
      (node (ref "SV3") (pin "15") (pinfunction "15_15") (pintype "passive"))
      (node (ref "U1") (pin "16") (pinfunction "PC1_16") (pintype "bidirectional"))
    )
    (net (code "60") (name "PC2") (class "Default")
      (node (ref "SV3") (pin "13") (pinfunction "13_13") (pintype "passive"))
      (node (ref "U1") (pin "17") (pinfunction "PC2_17") (pintype "bidirectional"))
    )
    (net (code "61") (name "PC3") (class "Default")
      (node (ref "SV3") (pin "11") (pinfunction "11_11") (pintype "passive"))
      (node (ref "U1") (pin "18") (pinfunction "PC3_18") (pintype "bidirectional"))
    )
    (net (code "62") (name "PC4") (class "Default")
      (node (ref "SV3") (pin "10") (pinfunction "10_10") (pintype "passive"))
      (node (ref "U1") (pin "33") (pinfunction "PC4_33") (pintype "bidirectional"))
    )
    (net (code "63") (name "PC5") (class "Default")
      (node (ref "SV3") (pin "12") (pinfunction "12_12") (pintype "passive"))
      (node (ref "U1") (pin "34") (pinfunction "PC5_34") (pintype "bidirectional"))
    )
    (net (code "64") (name "PE7") (class "Default")
      (node (ref "SV3") (pin "20") (pinfunction "20_20") (pintype "passive"))
      (node (ref "U1") (pin "38") (pinfunction "PE7_38") (pintype "bidirectional"))
    )
    (net (code "65") (name "PE8") (class "Default")
      (node (ref "SV3") (pin "22") (pinfunction "22_22") (pintype "passive"))
      (node (ref "U1") (pin "39") (pinfunction "PE8_39") (pintype "bidirectional"))
    )
    (net (code "66") (name "PE9") (class "Default")
      (node (ref "SV3") (pin "24") (pinfunction "24_24") (pintype "passive"))
      (node (ref "U1") (pin "40") (pinfunction "PE9_40") (pintype "bidirectional"))
    )
    (net (code "67") (name "PE10") (class "Default")
      (node (ref "SV3") (pin "26") (pinfunction "26_26") (pintype "passive"))
      (node (ref "U1") (pin "41") (pinfunction "PE10_41") (pintype "bidirectional"))
    )
    (net (code "68") (name "PE11") (class "Default")
      (node (ref "SV3") (pin "28") (pinfunction "28_28") (pintype "passive"))
      (node (ref "U1") (pin "42") (pinfunction "PE11_42") (pintype "bidirectional"))
    )
    (net (code "69") (name "PE12") (class "Default")
      (node (ref "SV3") (pin "30") (pinfunction "30_30") (pintype "passive"))
      (node (ref "U1") (pin "43") (pinfunction "PE12_43") (pintype "bidirectional"))
    )
    (net (code "70") (name "PE13") (class "Default")
      (node (ref "SV3") (pin "32") (pinfunction "32_32") (pintype "passive"))
      (node (ref "U1") (pin "44") (pinfunction "PE13_44") (pintype "bidirectional"))
    )
    (net (code "71") (name "PE14") (class "Default")
      (node (ref "SV3") (pin "34") (pinfunction "34_34") (pintype "passive"))
      (node (ref "U1") (pin "45") (pinfunction "PE14_45") (pintype "bidirectional"))
    )
    (net (code "72") (name "PE15") (class "Default")
      (node (ref "SV3") (pin "36") (pinfunction "36_36") (pintype "passive"))
      (node (ref "U1") (pin "46") (pinfunction "PE15_46") (pintype "bidirectional"))
    )
    (net (code "73") (name "SWCLK") (class "Default")
      (node (ref "SV6") (pin "2") (pinfunction "2_2") (pintype "passive"))
      (node (ref "U1") (pin "76") (pinfunction "PA14_76") (pintype "bidirectional"))
    )
    (net (code "74") (name "SWDIO") (class "Default")
      (node (ref "SV6") (pin "4") (pinfunction "4_4") (pintype "passive"))
      (node (ref "U1") (pin "72") (pinfunction "PA13_72") (pintype "bidirectional"))
    )
    (net (code "75") (name "SWO") (class "Default")
      (node (ref "SV6") (pin "6") (pinfunction "6_6") (pintype "passive"))
      (node (ref "SV7") (pin "1") (pinfunction "1_1") (pintype "passive"))
    )
    (net (code "76") (name "VCC") (class "Default")
      (node (ref "C15") (pin "1") (pinfunction "1_1") (pintype "passive"))
      (node (ref "IC3") (pin "8") (pinfunction "VIN_8") (pintype "input"))
      (node (ref "JP1") (pin "1") (pinfunction "1_1") (pintype "passive"))
      (node (ref "R10") (pin "2") (pinfunction "2_2") (pintype "passive"))
    )
    (net (code "77") (name "unconnected-(IC3-NC_1-Pad4)") (class "Default")
      (node (ref "IC3") (pin "4") (pinfunction "NC_1_4") (pintype "bidirectional"))
    )
    (net (code "78") (name "unconnected-(IC3-NC_2-Pad5)") (class "Default")
      (node (ref "IC3") (pin "5") (pinfunction "NC_2_5") (pintype "bidirectional"))
    )
    (net (code "79") (name "unconnected-(S1-P-Pad3)") (class "Default")
      (node (ref "S1") (pin "3") (pinfunction "P_3") (pintype "passive"))
    )
    (net (code "80") (name "unconnected-(SV3-Pad33)") (class "Default")
      (node (ref "SV3") (pin "33") (pinfunction "33_33") (pintype "passive"))
    )
    (net (code "81") (name "unconnected-(SV3-Pad35)") (class "Default")
      (node (ref "SV3") (pin "35") (pinfunction "35_35") (pintype "passive"))
    )
    (net (code "82") (name "unconnected-(SV3-Pad37)") (class "Default")
      (node (ref "SV3") (pin "37") (pinfunction "37_37") (pintype "passive"))
    )
    (net (code "83") (name "unconnected-(SV4-Pad5)") (class "Default")
      (node (ref "SV4") (pin "5") (pinfunction "5_5") (pintype "passive"))
    )
    (net (code "84") (name "unconnected-(U1A-PA8-Pad67)") (class "Default")
      (node (ref "U1") (pin "67") (pinfunction "PA8_67") (pintype "bidirectional"))
    )
    (net (code "85") (name "unconnected-(U1A-PA9-Pad68)") (class "Default")
      (node (ref "U1") (pin "68") (pinfunction "PA9_68") (pintype "bidirectional"))
    )
    (net (code "86") (name "unconnected-(U1A-PA10-Pad69)") (class "Default")
      (node (ref "U1") (pin "69") (pinfunction "PA10_69") (pintype "bidirectional"))
    )
    (net (code "87") (name "unconnected-(U1A-PA11-Pad70)") (class "Default")
      (node (ref "U1") (pin "70") (pinfunction "PA11_70") (pintype "bidirectional"))
    )
    (net (code "88") (name "unconnected-(U1A-PA12-Pad71)") (class "Default")
      (node (ref "U1") (pin "71") (pinfunction "PA12_71") (pintype "bidirectional"))
    )
    (net (code "89") (name "unconnected-(U1A-PB6-Pad92)") (class "Default")
      (node (ref "U1") (pin "92") (pinfunction "PB6_92") (pintype "bidirectional"))
    )
    (net (code "90") (name "unconnected-(U1A-PB7-Pad93)") (class "Default")
      (node (ref "U1") (pin "93") (pinfunction "PB7_93") (pintype "bidirectional"))
    )
    (net (code "91") (name "unconnected-(U1A-PB14-Pad53)") (class "Default")
      (node (ref "U1") (pin "53") (pinfunction "PB14_53") (pintype "bidirectional"))
    )
    (net (code "92") (name "unconnected-(U1B-PC8-Pad65)") (class "Default")
      (node (ref "U1") (pin "65") (pinfunction "PC8_65") (pintype "bidirectional"))
    )
    (net (code "93") (name "unconnected-(U1B-PC9-Pad66)") (class "Default")
      (node (ref "U1") (pin "66") (pinfunction "PC9_66") (pintype "bidirectional"))
    )
    (net (code "94") (name "unconnected-(U1B-PC11-Pad79)") (class "Default")
      (node (ref "U1") (pin "79") (pinfunction "PC11_79") (pintype "bidirectional"))
    )
    (net (code "95") (name "unconnected-(U1B-PC13-Pad7)") (class "Default")
      (node (ref "U1") (pin "7") (pinfunction "PC13_7") (pintype "bidirectional"))
    )
    (net (code "96") (name "unconnected-(U1B-PC14-Pad8)") (class "Default")
      (node (ref "U1") (pin "8") (pinfunction "PC14_8") (pintype "bidirectional"))
    )
    (net (code "97") (name "unconnected-(U1B-PC15-Pad9)") (class "Default")
      (node (ref "U1") (pin "9") (pinfunction "PC15_9") (pintype "bidirectional"))
    )
    (net (code "98") (name "unconnected-(U1B-PD1-Pad82)") (class "Default")
      (node (ref "U1") (pin "82") (pinfunction "PD1_82") (pintype "bidirectional"))
    )
    (net (code "99") (name "unconnected-(U1B-PD2-Pad83)") (class "Default")
      (node (ref "U1") (pin "83") (pinfunction "PD2_83") (pintype "bidirectional"))
    )
    (net (code "100") (name "unconnected-(U1B-PD3-Pad84)") (class "Default")
      (node (ref "U1") (pin "84") (pinfunction "PD3_84") (pintype "bidirectional"))
    )
    (net (code "101") (name "unconnected-(U1B-PD4-Pad85)") (class "Default")
      (node (ref "U1") (pin "85") (pinfunction "PD4_85") (pintype "bidirectional"))
    )
    (net (code "102") (name "unconnected-(U1B-PD5-Pad86)") (class "Default")
      (node (ref "U1") (pin "86") (pinfunction "PD5_86") (pintype "bidirectional"))
    )
    (net (code "103") (name "unconnected-(U1B-PD6-Pad87)") (class "Default")
      (node (ref "U1") (pin "87") (pinfunction "PD6_87") (pintype "bidirectional"))
    )
    (net (code "104") (name "unconnected-(U1B-PD7-Pad88)") (class "Default")
      (node (ref "U1") (pin "88") (pinfunction "PD7_88") (pintype "bidirectional"))
    )
    (net (code "105") (name "unconnected-(U1B-PD8-Pad55)") (class "Default")
      (node (ref "U1") (pin "55") (pinfunction "PD8_55") (pintype "bidirectional"))
    )
    (net (code "106") (name "unconnected-(U1B-PD9-Pad56)") (class "Default")
      (node (ref "U1") (pin "56") (pinfunction "PD9_56") (pintype "bidirectional"))
    )
    (net (code "107") (name "unconnected-(U1B-PD10-Pad57)") (class "Default")
      (node (ref "U1") (pin "57") (pinfunction "PD10_57") (pintype "bidirectional"))
    )
    (net (code "108") (name "unconnected-(U1B-PD11-Pad58)") (class "Default")
      (node (ref "U1") (pin "58") (pinfunction "PD11_58") (pintype "bidirectional"))
    )
    (net (code "109") (name "unconnected-(U1B-PD12-Pad59)") (class "Default")
      (node (ref "U1") (pin "59") (pinfunction "PD12_59") (pintype "bidirectional"))
    )
    (net (code "110") (name "unconnected-(U1B-PD13-Pad60)") (class "Default")
      (node (ref "U1") (pin "60") (pinfunction "PD13_60") (pintype "bidirectional"))
    )
    (net (code "111") (name "unconnected-(U1B-PD14-Pad61)") (class "Default")
      (node (ref "U1") (pin "61") (pinfunction "PD14_61") (pintype "bidirectional"))
    )
    (net (code "112") (name "unconnected-(U1B-PD15-Pad62)") (class "Default")
      (node (ref "U1") (pin "62") (pinfunction "PD15_62") (pintype "bidirectional"))
    )
    (net (code "113") (name "unconnected-(U1C-PE0-Pad97)") (class "Default")
      (node (ref "U1") (pin "97") (pinfunction "PE0_97") (pintype "bidirectional"))
    )
    (net (code "114") (name "unconnected-(U1C-PE1-Pad98)") (class "Default")
      (node (ref "U1") (pin "98") (pinfunction "PE1_98") (pintype "bidirectional"))
    )
    (net (code "115") (name "unconnected-(U1C-PE2-Pad1)") (class "Default")
      (node (ref "U1") (pin "1") (pinfunction "PE2_1") (pintype "bidirectional"))
    )
    (net (code "116") (name "unconnected-(U1C-PE3-Pad2)") (class "Default")
      (node (ref "U1") (pin "2") (pinfunction "PE3_2") (pintype "bidirectional"))
    )
    (net (code "117") (name "unconnected-(U1C-PE4-Pad3)") (class "Default")
      (node (ref "U1") (pin "3") (pinfunction "PE4_3") (pintype "bidirectional"))
    )
    (net (code "118") (name "unconnected-(U1C-PE5-Pad4)") (class "Default")
      (node (ref "U1") (pin "4") (pinfunction "PE5_4") (pintype "bidirectional"))
    )
    (net (code "119") (name "unconnected-(U1C-PE6-Pad5)") (class "Default")
      (node (ref "U1") (pin "5") (pinfunction "PE6_5") (pintype "bidirectional"))
    )
    (net (code "120") (name "unconnected-(U1C-PH0-Pad12)") (class "Default")
      (node (ref "U1") (pin "12") (pinfunction "PH0_12") (pintype "bidirectional"))
    )
    (net (code "121") (name "unconnected-(U1C-PH1-Pad13)") (class "Default")
      (node (ref "U1") (pin "13") (pinfunction "PH1_13") (pintype "bidirectional"))
    )
    (net (code "122") (name "unconnected-(U2-SWITCH-PadP$2_SWITCH)") (class "Default")
      (node (ref "U2") (pin "P$2_SWITCH") (pinfunction "SWITCH_P$2_SWITCH") (pintype "passive"))
    )
    (net (code "123") (name "unconnected-(U3-SWITCH-PadP$2_SWITCH)") (class "Default")
      (node (ref "U3") (pin "P$2_SWITCH") (pinfunction "SWITCH_P$2_SWITCH") (pintype "passive"))
    )
  )
)
